# 1_Supply.net
KiCad netlist of a schematic drawn in Altium Designer
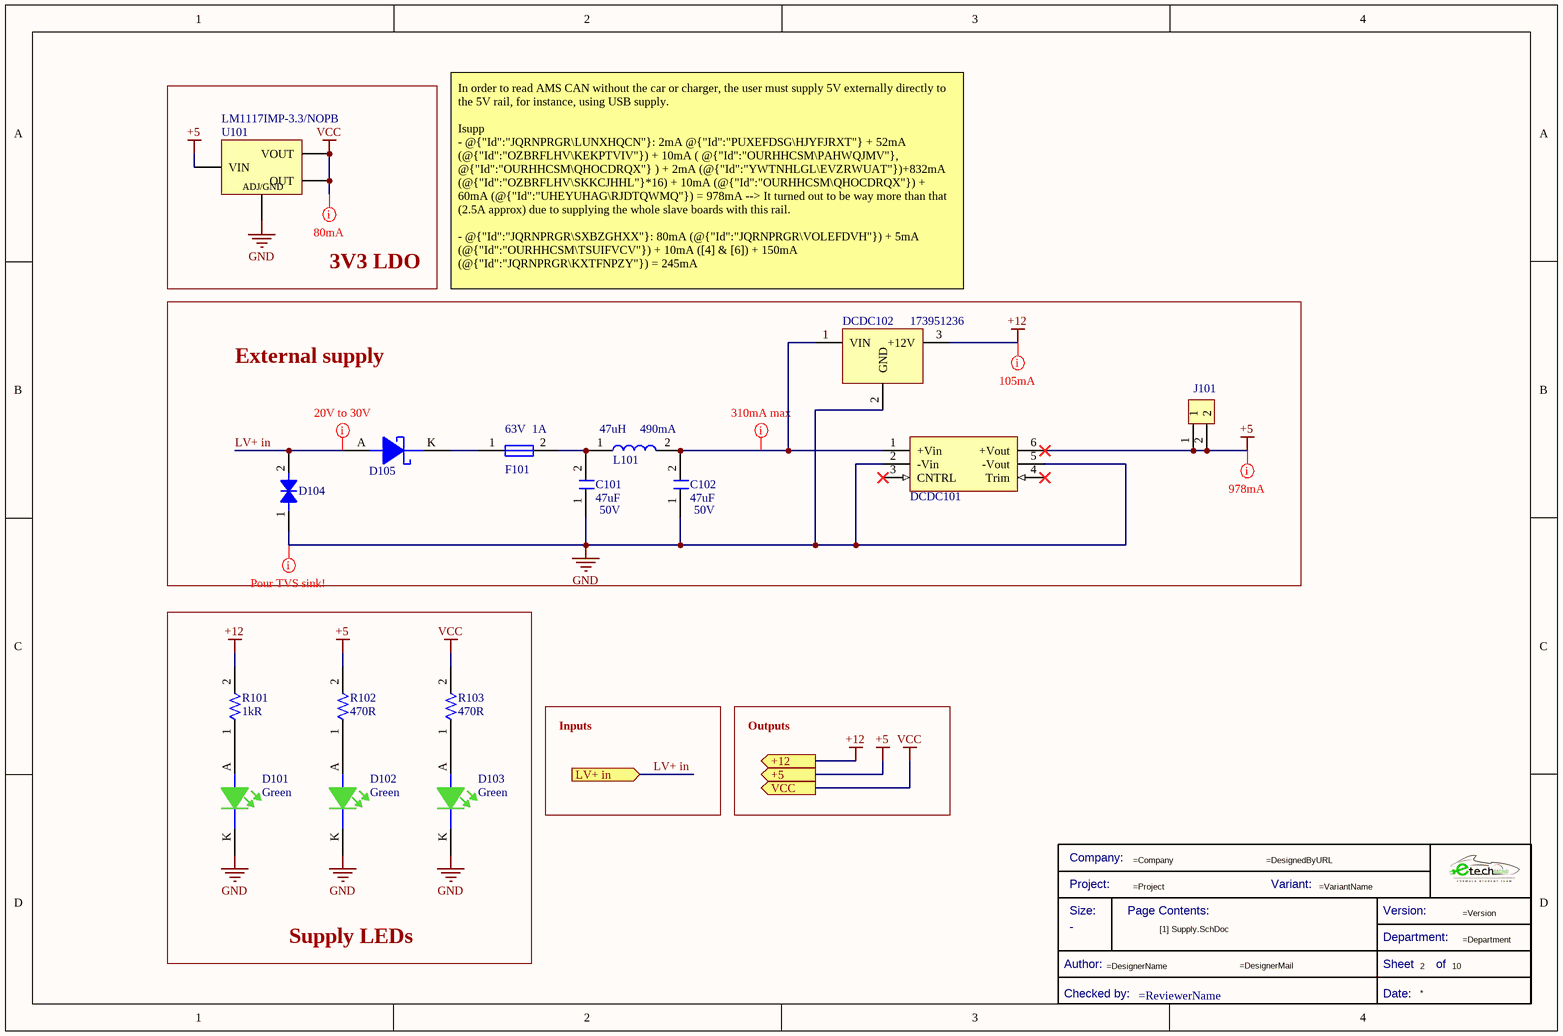
[diagram p0: [1] Supply.SchDoc]

(export (version "E")
  (design (tool "Eeschema 10.0.6"))
  (components
    (comp (ref "*")
      (value "Title Block_template")
      (description "Standard Title Block")
      (fields (field (name "SIZE") "-"))
      (libsource (lib "e-Tech_Racing") (part "Title Block_template"))
    )
    (comp (ref "C101")
      (value "GRJ32ER71H106KE11L")
      (footprint "C10u-50V-1210FNPMLCC-X7R")
      (description "Multilayer Ceramic Capacitors MLCC - SMD/SMT 1210 10uF 50volts X7R +/-10% Soft Term")
      (fields
        (field (name "MANUFACTURER") "Murata")
        (field (name "VOLTAGE RATING") "50V")
        (field (name "TOLERANCE") "10%")
        (field (name "CAPACITANCE") "47uF")
        (field (name ".CREATOR") "DR")
      )
      (libsource (lib "Passives") (part "C10u-50V-1210FNPMLCC-X7R"))
    )
    (comp (ref "C102")
      (value "GRJ32ER71H106KE11L")
      (footprint "C10u-50V-1210FNPMLCC-X7R")
      (description "Multilayer Ceramic Capacitors MLCC - SMD/SMT 1210 10uF 50volts X7R +/-10% Soft Term")
      (fields
        (field (name "MANUFACTURER") "Murata")
        (field (name "VOLTAGE RATING") "50V")
        (field (name "TOLERANCE") "10%")
        (field (name "CAPACITANCE") "47uF")
        (field (name ".CREATOR") "DR")
      )
      (libsource (lib "Passives") (part "C10u-50V-1210FNPMLCC-X7R"))
    )
    (comp (ref "D101")
      (value "150080VS75000")
      (footprint "LED_0805_WE")
      (description "Led, Green, 570 Nm, 2 V, 30 Ma, 40 Mcd Rohs Compliant: Yes")
      (fields (field (name "COLOR") "Green") (field (name ".CREATOR") "DR"))
      (libsource (lib "Semiconductor") (part "LEDVS-0805-40"))
    )
    (comp (ref "D102")
      (value "150080VS75000")
      (footprint "LED_0805_WE")
      (description "Led, Green, 570 Nm, 2 V, 30 Ma, 40 Mcd Rohs Compliant: Yes")
      (fields (field (name "COLOR") "Green") (field (name ".CREATOR") "DR"))
      (libsource (lib "Semiconductor") (part "LEDVS-0805-40"))
    )
    (comp (ref "D103")
      (value "150080VS75000")
      (footprint "LED_0805_WE")
      (description "Led, Green, 570 Nm, 2 V, 30 Ma, 40 Mcd Rohs Compliant: Yes")
      (fields (field (name "COLOR") "Green") (field (name ".CREATOR") "DR"))
      (libsource (lib "Semiconductor") (part "LEDVS-0805-40"))
    )
    (comp (ref "D104")
      (value "824551301")
      (footprint "DTVS-DO-214AB")
      (description "TVS diode [Würth Elektronik] 824551301 TVS diode")
      (fields (field (name "MANUFACTURER") "Wurth Electronics") (field (name ".CREATOR") "DO"))
      (libsource (lib "Filter components") (part "DTVS-40V-DO-214AB"))
    )
    (comp (ref "D105")
      (value "MBR0530")
      (footprint "DSC-SOD123")
      (description "VR=30V IF=500mA 30pF P=410mW")
      (fields (field (name ".CREATOR") "GP"))
      (libsource (lib "Filter components") (part "DSC-0.5/30-SOD123"))
    )
    (comp (ref "DCDC101")
      (value "RPA60-2405SFW")
      (footprint "DCDC60W-24")
      (description "60W DC/DC-Converter 'POWERLINE' 2 x1 1.5kV reg 4: ; V. In: 9-36; V. Out: 05; mA. Out: 12000")
      (fields
        (field (name "MANUFACTURER") "Recom")
        (field (name "MANUFACTURER PART NUMBER") "RPA60-2405SFW/N")
        (field (name ".CREATOR") "GP")
      )
      (libsource (lib "Semiconductor") (part "DCDC60W-2405"))
    )
    (comp (ref "DCDC102")
      (value "173951236")
      (footprint "DCDC_Magi3c")
      (description "Fdsm Fixed Step Down Regulator M")
      (libsource (lib "Semiconductor") (part "DCDC-36V/12V-0.5A"))
    )
    (comp (ref "F101")
      (value "0437001.WRA")
      (footprint "Fuse_1206")
      (description "Fuse Chip Fast Acting 1A 63V SMD Solder Pad 1206 Ceramic T/R Automotive")
      (fields
        (field (name "MANUFACTURER") "Littelfuse")
        (field (name "CURRENT RATING") "1A")
        (field (name "VOLTAGE RATING (DC)") "63V")
        (field (name ".CREATOR") "DO")
      )
      (libsource (lib "Filter components") (part "Fuse_1A_63V_1206"))
    )
    (comp (ref "J101")
      (value "61300211121")
      (footprint "J_Pinheader_1x2")
      (description "CONN HEADER 2 POS 2.54")
      (fields (field (name "MANUFACTURER") "Molex") (field (name ".CREATOR") "GP"))
      (libsource (lib "Electromechanical") (part "J_Jumper"))
    )
    (comp (ref "L101")
      (value "CDC5D23BNP-470KC")
      (footprint "L_47u-490mA_CF")
      (description "Inductor Power Unshielded Wirewound 47uH 10% 100KHz Ferrite 490mA 546mOhm DCR T/R")
      (fields
        (field (name "MANUFACTURER") "Sumida")
        (field (name "TOLERANCE") "10%")
        (field (name "CURRENT RATING") "490mA")
        (field (name "INDUCTANCE") "47uH")
        (field (name ".CREATOR") "GP")
      )
      (libsource (lib "Passives") (part "L_47u-490mA_CF"))
    )
    (comp (ref "R101")
      (value "CR0805-JW-102ELF")
      (footprint "R0805FTK")
      (description "Res Thick Film 0805 1K Ohm 5% 1/8W ±200ppm/°C Molded SMD SMD Paper Tape on Plastic Reel")
      (fields
        (field (name "TOLERANCE") "5%")
        (field (name "RESISTANCE") "1kR")
        (field (name ".CREATOR") "GP")
      )
      (libsource (lib "Passives") (part "R1k-0805FTK"))
    )
    (comp (ref "R102")
      (value "CR0805-FX-4700GLF")
      (footprint "R0805FTK")
      (description "Res Thick Film 0805 470 Ohm 1% 1/8W ±100ppm/°C Molded SMD SMD Paper Tape on Plastic Reel")
      (fields
        (field (name "TOLERANCE") "1%")
        (field (name "RESISTANCE") "470R")
        (field (name ".CREATOR") "DR")
      )
      (libsource (lib "Passives") (part "R470-0805FTK"))
    )
    (comp (ref "R103")
      (value "CR0805-FX-4700GLF")
      (footprint "R0805FTK")
      (description "Res Thick Film 0805 470 Ohm 1% 1/8W ±100ppm/°C Molded SMD SMD Paper Tape on Plastic Reel")
      (fields
        (field (name "TOLERANCE") "1%")
        (field (name "RESISTANCE") "470R")
        (field (name ".CREATOR") "DR")
      )
      (libsource (lib "Passives") (part "R470-0805FTK"))
    )
    (comp (ref "U101")
      (value "LM1117IMP-3.3/NOPB")
      (footprint "LDO_10V-0.8/3V3-SOT223")
      (description "LDO Regulator Pos 3.3V 0.8A 4-Pin(3+Tab) SOT-223 T/R / IC REG LDO 3.3V 0.8A SOT223")
      (fields
        (field (name "MANUFACTURER") "Texas Instruments")
        (field (name "MANUFACTURER PART NUMBER") "LM1117IMP-3.3/NOPB")
        (field (name ".CREATOR") "GP")
      )
      (libsource (lib "Semiconductor") (part "LDO_10V-0.8/3V3-SOT223"))
    )
  )
  (nets
    (net (code "1") (name "+5") (class "Default")
      (node (ref "DCDC101") (pin "6") (pinfunction "+Vout_6") (pintype "power_in"))
      (node (ref "J101") (pin "1") (pinfunction "1_1") (pintype "passive"))
      (node (ref "J101") (pin "2") (pinfunction "2_2") (pintype "passive"))
      (node (ref "R102") (pin "2") (pinfunction "2_2") (pintype "passive"))
      (node (ref "U101") (pin "3") (pinfunction "VIN_3") (pintype "passive"))
    )
    (net (code "2") (name "+12") (class "Default")
      (node (ref "DCDC102") (pin "3") (pinfunction "+12V_3") (pintype "passive"))
      (node (ref "R101") (pin "2") (pinfunction "2_2") (pintype "passive"))
    )
    (net (code "3") (name "/LV+ in") (class "Default")
      (node (ref "D104") (pin "2") (pinfunction "2_2") (pintype "passive"))
      (node (ref "D105") (pin "A") (pinfunction "A_A") (pintype "passive"))
    )
    (net (code "4") (name "GND") (class "Default")
      (node (ref "C101") (pin "1") (pinfunction "1_1") (pintype "passive"))
      (node (ref "C102") (pin "1") (pinfunction "1_1") (pintype "passive"))
      (node (ref "D101") (pin "K") (pinfunction "K_K") (pintype "passive"))
      (node (ref "D102") (pin "K") (pinfunction "K_K") (pintype "passive"))
      (node (ref "D103") (pin "K") (pinfunction "K_K") (pintype "passive"))
      (node (ref "D104") (pin "1") (pinfunction "1_1") (pintype "passive"))
      (node (ref "DCDC101") (pin "2") (pinfunction "-Vin_2") (pintype "power_in"))
      (node (ref "DCDC101") (pin "5") (pinfunction "-Vout_5") (pintype "power_in"))
      (node (ref "DCDC102") (pin "2") (pinfunction "GND_2") (pintype "passive"))
      (node (ref "U101") (pin "1") (pinfunction "ADJ/GND_1") (pintype "passive"))
    )
    (net (code "5") (name "Net-(C101-Pad2)") (class "Default")
      (node (ref "C101") (pin "2") (pinfunction "2_2") (pintype "passive"))
      (node (ref "F101") (pin "2") (pinfunction "2_2") (pintype "passive"))
      (node (ref "L101") (pin "1") (pinfunction "1_1") (pintype "passive"))
    )
    (net (code "6") (name "Net-(D101-PadA)") (class "Default")
      (node (ref "D101") (pin "A") (pinfunction "A_A") (pintype "passive"))
      (node (ref "R101") (pin "1") (pinfunction "1_1") (pintype "passive"))
    )
    (net (code "7") (name "Net-(D102-PadA)") (class "Default")
      (node (ref "D102") (pin "A") (pinfunction "A_A") (pintype "passive"))
      (node (ref "R102") (pin "1") (pinfunction "1_1") (pintype "passive"))
    )
    (net (code "8") (name "Net-(D103-PadA)") (class "Default")
      (node (ref "D103") (pin "A") (pinfunction "A_A") (pintype "passive"))
      (node (ref "R103") (pin "1") (pinfunction "1_1") (pintype "passive"))
    )
    (net (code "9") (name "Net-(D105-PadK)") (class "Default")
      (node (ref "D105") (pin "K") (pinfunction "K_K") (pintype "passive"))
      (node (ref "F101") (pin "1") (pinfunction "1_1") (pintype "passive"))
    )
    (net (code "10") (name "Net-(DCDC101-+Vin)") (class "Default")
      (node (ref "C102") (pin "2") (pinfunction "2_2") (pintype "passive"))
      (node (ref "DCDC101") (pin "1") (pinfunction "+Vin_1") (pintype "power_in"))
      (node (ref "DCDC102") (pin "1") (pinfunction "VIN_1") (pintype "passive"))
      (node (ref "L101") (pin "2") (pinfunction "2_2") (pintype "passive"))
    )
    (net (code "11") (name "VCC") (class "Default")
      (node (ref "R103") (pin "2") (pinfunction "2_2") (pintype "passive"))
      (node (ref "U101") (pin "2") (pinfunction "OUT_2") (pintype "passive"))
      (node (ref "U101") (pin "4") (pinfunction "VOUT_4") (pintype "passive"))
    )
    (net (code "12") (name "unconnected-(DCDC101-CNTRL-Pad3)") (class "Default")
      (node (ref "DCDC101") (pin "3") (pinfunction "CNTRL_3") (pintype "input+no_connect"))
    )
    (net (code "13") (name "unconnected-(DCDC101-Trim-Pad4)") (class "Default")
      (node (ref "DCDC101") (pin "4") (pinfunction "Trim_4") (pintype "input+no_connect"))
    )
  )
)
